# EEGAmp_Thruhole.net
KiCad netlist of a schematic drawn in EAGLE
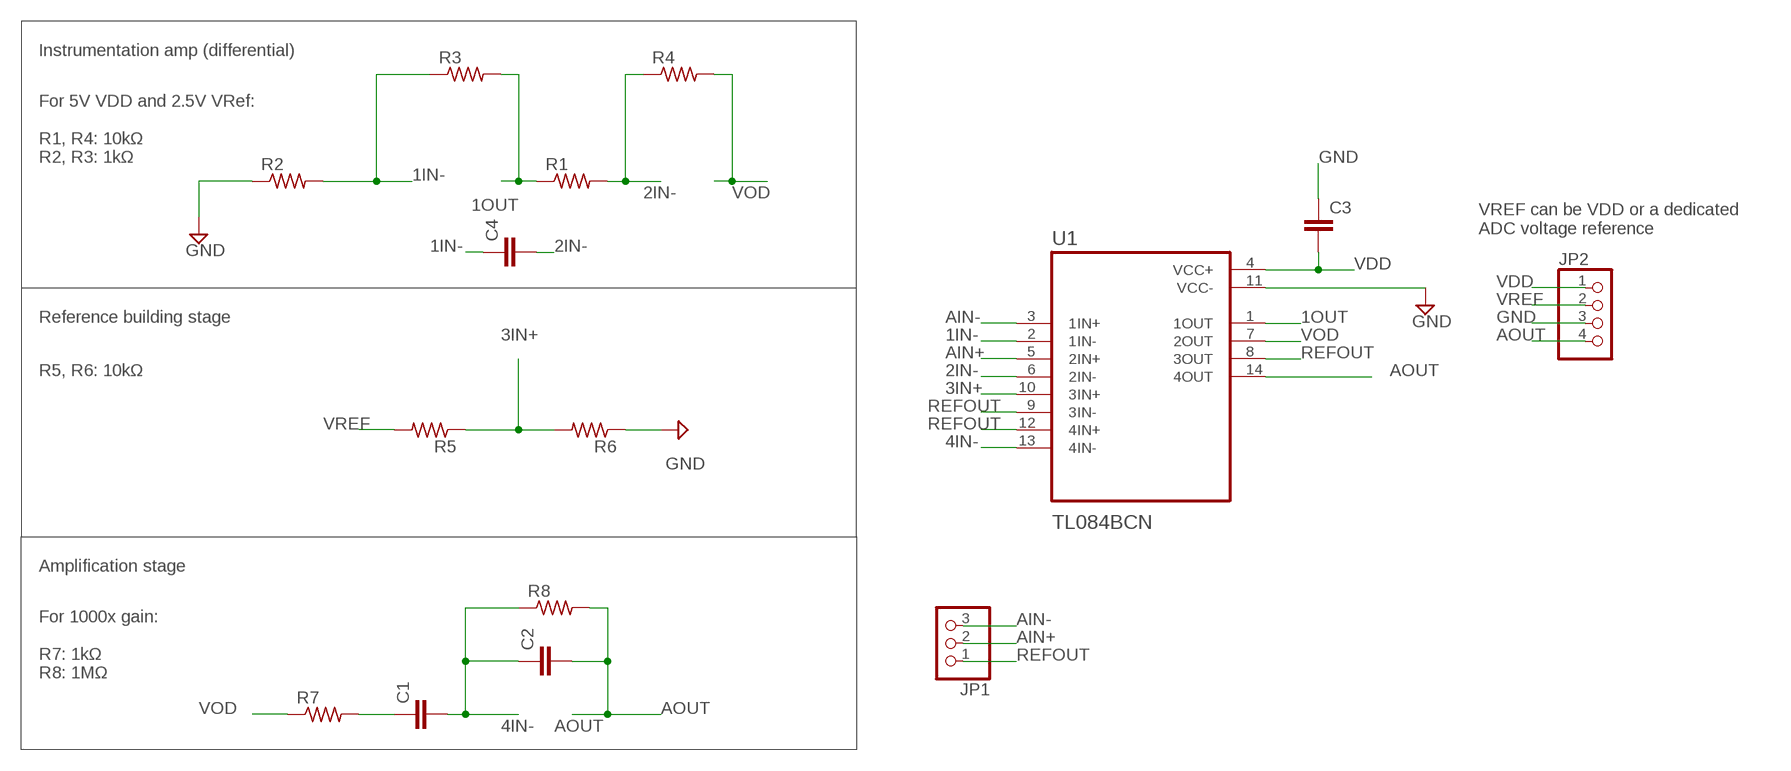
[diagram p0: schematic, sheet 1]

(export (version "E")
  (design (tool "Eeschema 10.0.6"))
  (components
    (comp (ref "C1")
      (value "C2.5/2")
      (footprint "eagle-import:C2.5-2")
      (libsource (lib "eagle-import") (part "C2.5/2"))
    )
    (comp (ref "C2")
      (value "C2.5/2")
      (footprint "eagle-import:C2.5-2")
      (libsource (lib "eagle-import") (part "C2.5/2"))
    )
    (comp (ref "C3")
      (value "C2.5/2")
      (footprint "eagle-import:C2.5-2")
      (libsource (lib "eagle-import") (part "C2.5/2"))
    )
    (comp (ref "C4")
      (value "C2.5/2")
      (footprint "eagle-import:C2.5-2")
      (libsource (lib "eagle-import") (part "C2.5/2"))
    )
    (comp (ref "JP1")
      (value "PINHD-1X3")
      (footprint "eagle-import:1X03")
      (libsource (lib "eagle-import") (part "PINHD-1X3"))
    )
    (comp (ref "JP2")
      (value "PINHD-1X4")
      (footprint "eagle-import:1X04")
      (libsource (lib "eagle-import") (part "PINHD-1X4"))
    )
    (comp (ref "R1")
      (value "R-US_0204/5")
      (footprint "eagle-import:0204_5")
      (libsource (lib "eagle-import") (part "R-US_0204/5"))
    )
    (comp (ref "R2")
      (value "R-US_0204/5")
      (footprint "eagle-import:0204_5")
      (libsource (lib "eagle-import") (part "R-US_0204/5"))
    )
    (comp (ref "R3")
      (value "R-US_0204/5")
      (footprint "eagle-import:0204_5")
      (libsource (lib "eagle-import") (part "R-US_0204/5"))
    )
    (comp (ref "R4")
      (value "R-US_0204/5")
      (footprint "eagle-import:0204_5")
      (libsource (lib "eagle-import") (part "R-US_0204/5"))
    )
    (comp (ref "R5")
      (value "R-US_0204/5")
      (footprint "eagle-import:0204_5")
      (libsource (lib "eagle-import") (part "R-US_0204/5"))
    )
    (comp (ref "R6")
      (value "R-US_0204/5")
      (footprint "eagle-import:0204_5")
      (libsource (lib "eagle-import") (part "R-US_0204/5"))
    )
    (comp (ref "R7")
      (value "R-US_0204/5")
      (footprint "eagle-import:0204_5")
      (libsource (lib "eagle-import") (part "R-US_0204/5"))
    )
    (comp (ref "R8")
      (value "R-US_0204/5")
      (footprint "eagle-import:0204_5")
      (libsource (lib "eagle-import") (part "R-US_0204/5"))
    )
    (comp (ref "U1")
      (value "TL084BCN")
      (footprint "eagle-import:DIP794W45P254L1969H508Q14")
      (fields (field (name "MF") "Texas Instruments"))
      (libsource (lib "eagle-import") (part "TL084BCN"))
    )
  )
  (nets
    (net (code "1") (name "/1IN-") (class "Default")
      (node (ref "C4") (pin "1") (pinfunction "1_1") (pintype "passive"))
      (node (ref "R2") (pin "2") (pinfunction "2_2") (pintype "passive"))
      (node (ref "R3") (pin "1") (pinfunction "1_1") (pintype "passive"))
      (node (ref "U1") (pin "2") (pinfunction "1IN-_2") (pintype "input"))
    )
    (net (code "2") (name "/1OUT") (class "Default")
      (node (ref "R1") (pin "1") (pinfunction "1_1") (pintype "passive"))
      (node (ref "R3") (pin "2") (pinfunction "2_2") (pintype "passive"))
      (node (ref "U1") (pin "1") (pinfunction "1OUT_1") (pintype "output"))
    )
    (net (code "3") (name "/2IN-") (class "Default")
      (node (ref "C4") (pin "2") (pinfunction "2_2") (pintype "passive"))
      (node (ref "R1") (pin "2") (pinfunction "2_2") (pintype "passive"))
      (node (ref "R4") (pin "1") (pinfunction "1_1") (pintype "passive"))
      (node (ref "U1") (pin "6") (pinfunction "2IN-_6") (pintype "input"))
    )
    (net (code "4") (name "/3IN+") (class "Default")
      (node (ref "R5") (pin "1") (pinfunction "1_1") (pintype "passive"))
      (node (ref "R6") (pin "2") (pinfunction "2_2") (pintype "passive"))
      (node (ref "U1") (pin "10") (pinfunction "3IN+_10") (pintype "input"))
    )
    (net (code "5") (name "/4IN-") (class "Default")
      (node (ref "C1") (pin "2") (pinfunction "2_2") (pintype "passive"))
      (node (ref "C2") (pin "1") (pinfunction "1_1") (pintype "passive"))
      (node (ref "R8") (pin "1") (pinfunction "1_1") (pintype "passive"))
      (node (ref "U1") (pin "13") (pinfunction "4IN-_13") (pintype "input"))
    )
    (net (code "6") (name "/AIN+") (class "Default")
      (node (ref "JP1") (pin "2") (pinfunction "2_2") (pintype "passive"))
      (node (ref "U1") (pin "5") (pinfunction "2IN+_5") (pintype "input"))
    )
    (net (code "7") (name "/AIN-") (class "Default")
      (node (ref "JP1") (pin "3") (pinfunction "3_3") (pintype "passive"))
      (node (ref "U1") (pin "3") (pinfunction "1IN+_3") (pintype "input"))
    )
    (net (code "8") (name "/AOUT") (class "Default")
      (node (ref "C2") (pin "2") (pinfunction "2_2") (pintype "passive"))
      (node (ref "JP2") (pin "4") (pinfunction "4_4") (pintype "passive"))
      (node (ref "R8") (pin "2") (pinfunction "2_2") (pintype "passive"))
      (node (ref "U1") (pin "14") (pinfunction "4OUT_14") (pintype "output"))
    )
    (net (code "9") (name "/REFOUT") (class "Default")
      (node (ref "JP1") (pin "1") (pinfunction "1_1") (pintype "passive"))
      (node (ref "U1") (pin "12") (pinfunction "4IN+_12") (pintype "input"))
      (node (ref "U1") (pin "8") (pinfunction "3OUT_8") (pintype "output"))
      (node (ref "U1") (pin "9") (pinfunction "3IN-_9") (pintype "input"))
    )
    (net (code "10") (name "/VDD") (class "Default")
      (node (ref "C3") (pin "2") (pinfunction "2_2") (pintype "passive"))
      (node (ref "JP2") (pin "1") (pinfunction "1_1") (pintype "passive"))
      (node (ref "U1") (pin "4") (pinfunction "VCC+_4") (pintype "power_in"))
    )
    (net (code "11") (name "/VOD") (class "Default")
      (node (ref "R4") (pin "2") (pinfunction "2_2") (pintype "passive"))
      (node (ref "R7") (pin "1") (pinfunction "1_1") (pintype "passive"))
      (node (ref "U1") (pin "7") (pinfunction "2OUT_7") (pintype "output"))
    )
    (net (code "12") (name "/VREF") (class "Default")
      (node (ref "JP2") (pin "2") (pinfunction "2_2") (pintype "passive"))
      (node (ref "R5") (pin "2") (pinfunction "2_2") (pintype "passive"))
    )
    (net (code "13") (name "GND") (class "Default")
      (node (ref "C3") (pin "1") (pinfunction "1_1") (pintype "passive"))
      (node (ref "JP2") (pin "3") (pinfunction "3_3") (pintype "passive"))
      (node (ref "R2") (pin "1") (pinfunction "1_1") (pintype "passive"))
      (node (ref "R6") (pin "1") (pinfunction "1_1") (pintype "passive"))
      (node (ref "U1") (pin "11") (pinfunction "VCC-_11") (pintype "power_in"))
    )
    (net (code "14") (name "Net-(C1-Pad1)") (class "Default")
      (node (ref "C1") (pin "1") (pinfunction "1_1") (pintype "passive"))
      (node (ref "R7") (pin "2") (pinfunction "2_2") (pintype "passive"))
    )
  )
)
